# Blinds_Motor_ESP32_w_endstops.net
KiCad netlist of a schematic drawn in EAGLE
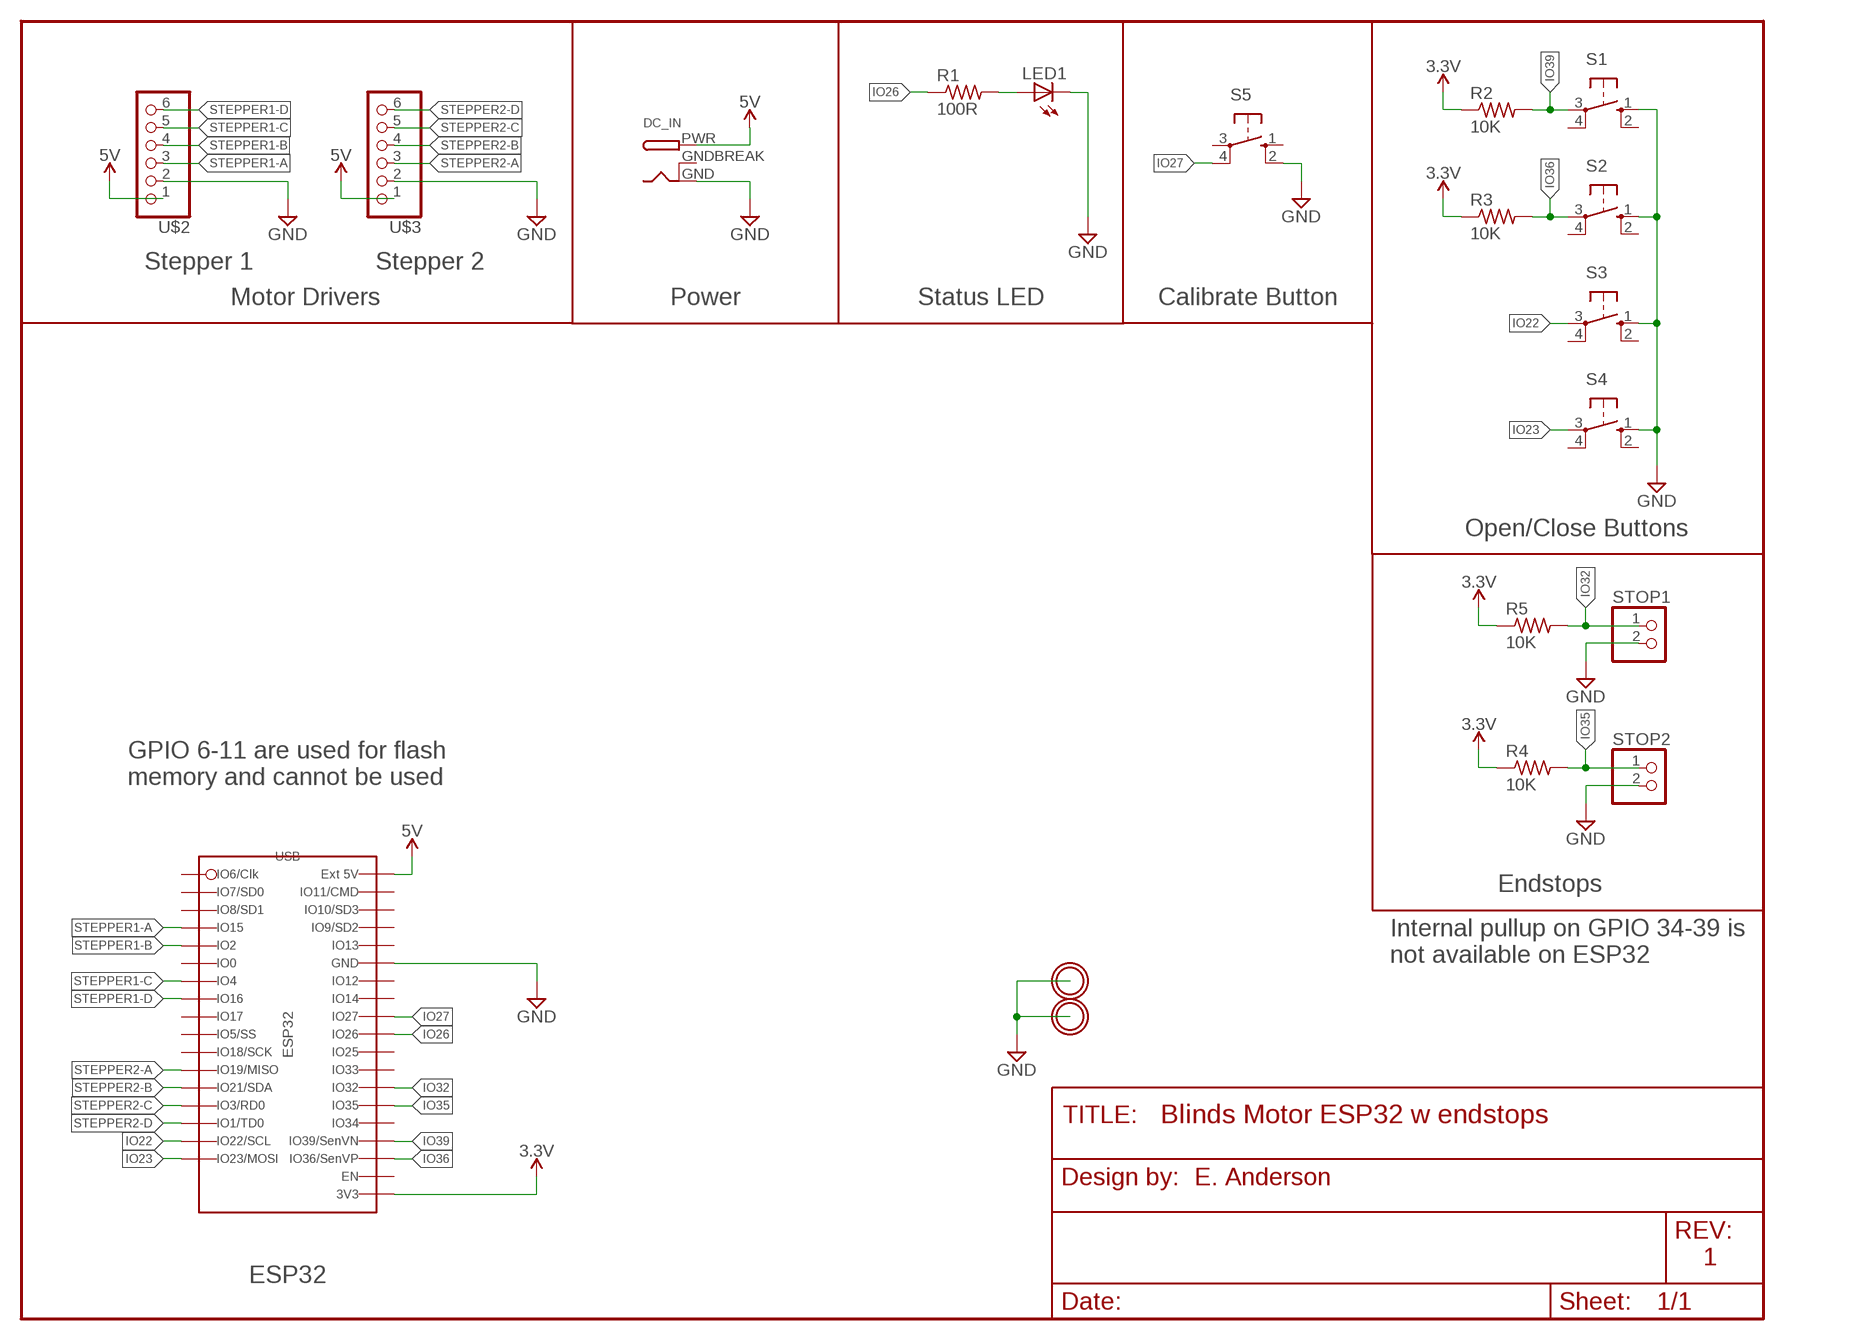
[diagram p0: schematic, sheet 1]

(export (version "E")
  (design (tool "Eeschema 10.0.6"))
  (components
    (comp (ref "DC_IN")
      (value "DCBARRELPTH")
      (footprint "eagle-import:DCJACK_2MM_PTH")
      (libsource (lib "eagle-import") (part "DCBARRELPTH"))
    )
    (comp (ref "LED1")
      (value "LED-CHIPLED_1206_LONG")
      (footprint "eagle-import:CHIPLED_1206_LONG")
      (libsource (lib "eagle-import") (part "LED-CHIPLED_1206_LONG"))
    )
    (comp (ref "R1")
      (value "100R")
      (footprint "eagle-import:R1206")
      (libsource (lib "eagle-import") (part "R_USR1206"))
    )
    (comp (ref "R2")
      (value "10K")
      (footprint "eagle-import:R1206")
      (libsource (lib "eagle-import") (part "R_USR1206"))
    )
    (comp (ref "R3")
      (value "10K")
      (footprint "eagle-import:R1206")
      (libsource (lib "eagle-import") (part "R_USR1206"))
    )
    (comp (ref "R4")
      (value "10K")
      (footprint "eagle-import:R1206")
      (libsource (lib "eagle-import") (part "R_USR1206"))
    )
    (comp (ref "R5")
      (value "10K")
      (footprint "eagle-import:R1206")
      (libsource (lib "eagle-import") (part "R_USR1206"))
    )
    (comp (ref "S1")
      (value "B3F-10XX")
      (footprint "eagle-import:B3F-10XX")
      (fields (field (name "MPN") "B3F-1000"))
      (libsource (lib "eagle-import") (part "B3F-10XX"))
    )
    (comp (ref "S2")
      (value "B3F-10XX")
      (footprint "eagle-import:B3F-10XX")
      (fields (field (name "MPN") "B3F-1000"))
      (libsource (lib "eagle-import") (part "B3F-10XX"))
    )
    (comp (ref "S3")
      (value "B3F-10XX")
      (footprint "eagle-import:B3F-10XX")
      (fields (field (name "MPN") "B3F-1000"))
      (libsource (lib "eagle-import") (part "B3F-10XX"))
    )
    (comp (ref "S4")
      (value "B3F-10XX")
      (footprint "eagle-import:B3F-10XX")
      (fields (field (name "MPN") "B3F-1000"))
      (libsource (lib "eagle-import") (part "B3F-10XX"))
    )
    (comp (ref "S5")
      (value "B3F-10XX")
      (footprint "eagle-import:B3F-10XX")
      (fields (field (name "MPN") "B3F-1000"))
      (libsource (lib "eagle-import") (part "B3F-10XX"))
    )
    (comp (ref "STOP1")
      (value "1X2_HEADER_LONG")
      (footprint "eagle-import:1X02")
      (libsource (lib "eagle-import") (part "1X2_HEADER_LONG"))
    )
    (comp (ref "STOP2")
      (value "1X2_HEADER_LONG")
      (footprint "eagle-import:1X02")
      (libsource (lib "eagle-import") (part "1X2_HEADER_LONG"))
    )
    (comp (ref "U$2")
      (value "Stepper 1")
      (footprint "eagle-import:1X06")
      (libsource (lib "eagle-import") (part "1X6_HEADER_LONG"))
    )
    (comp (ref "U$3")
      (value "Stepper 2")
      (footprint "eagle-import:1X06")
      (libsource (lib "eagle-import") (part "1X6_HEADER_LONG"))
    )
    (comp (ref "U$5")
      (value "MICROBUILDER_MOUNTINGHOLE3.0THIN")
      (footprint "eagle-import:MICROBUILDER_MOUNTINGHOLE_3.0_PLATEDTHIN")
      (libsource (lib "eagle-import") (part "MICROBUILDER_MOUNTINGHOLE3.0THIN"))
    )
    (comp (ref "U$6")
      (value "MICROBUILDER_MOUNTINGHOLE3.0THIN")
      (footprint "eagle-import:MICROBUILDER_MOUNTINGHOLE_3.0_PLATEDTHIN")
      (libsource (lib "eagle-import") (part "MICROBUILDER_MOUNTINGHOLE3.0THIN"))
    )
    (comp (ref "U$7")
      (value "ESP32-DEV")
      (footprint "eagle-import:ESP32_DEV")
      (libsource (lib "eagle-import") (part "ESP32-DEV"))
    )
  )
  (nets
    (net (code "1") (name "/GNDBREAK") (class "Default")
      (node (ref "DC_IN") (pin "GNDBREAK") (pinfunction "GNDBREAK_GNDBREAK") (pintype "power_in"))
    )
    (net (code "2") (name "3.3V") (class "Default")
      (node (ref "R2") (pin "1") (pinfunction "1_1") (pintype "passive"))
      (node (ref "R3") (pin "1") (pinfunction "1_1") (pintype "passive"))
      (node (ref "R4") (pin "1") (pinfunction "1_1") (pintype "passive"))
      (node (ref "R5") (pin "1") (pinfunction "1_1") (pintype "passive"))
      (node (ref "U$7") (pin "3V3") (pinfunction "3V3_3V3") (pintype "power_in"))
    )
    (net (code "3") (name "5V") (class "Default")
      (node (ref "DC_IN") (pin "PWR") (pinfunction "PWR_PWR") (pintype "power_in"))
      (node (ref "U$2") (pin "1") (pinfunction "1_1") (pintype "passive"))
      (node (ref "U$3") (pin "1") (pinfunction "1_1") (pintype "passive"))
      (node (ref "U$7") (pin "5V") (pinfunction "EXT_5V_5V") (pintype "power_in"))
    )
    (net (code "4") (name "GND") (class "Default")
      (node (ref "DC_IN") (pin "GND") (pinfunction "GND_GND") (pintype "power_in"))
      (node (ref "LED1") (pin "C") (pinfunction "C_C") (pintype "passive"))
      (node (ref "S1") (pin "1") (pinfunction "S_1") (pintype "passive"))
      (node (ref "S2") (pin "1") (pinfunction "S_1") (pintype "passive"))
      (node (ref "S3") (pin "1") (pinfunction "S_1") (pintype "passive"))
      (node (ref "S4") (pin "1") (pinfunction "S_1") (pintype "passive"))
      (node (ref "S5") (pin "2") (pinfunction "S1_2") (pintype "passive"))
      (node (ref "STOP1") (pin "2") (pinfunction "2_2") (pintype "passive"))
      (node (ref "STOP2") (pin "2") (pinfunction "2_2") (pintype "passive"))
      (node (ref "U$2") (pin "2") (pinfunction "2_2") (pintype "passive"))
      (node (ref "U$3") (pin "2") (pinfunction "2_2") (pintype "passive"))
      (node (ref "U$7") (pin "GND") (pinfunction "GND1_GND") (pintype "bidirectional"))
      (node (ref "U$7") (pin "GND1") (pinfunction "GND1_GND1") (pintype "bidirectional"))
      (node (ref "U$7") (pin "GND2") (pinfunction "GND1_GND2") (pintype "bidirectional"))
    )
    (net (code "5") (name "IO22") (class "Default")
      (node (ref "S3") (pin "3") (pinfunction "P_3") (pintype "passive"))
      (node (ref "U$7") (pin "IO22") (pinfunction "IO22_IO22") (pintype "bidirectional"))
    )
    (net (code "6") (name "IO23") (class "Default")
      (node (ref "S4") (pin "3") (pinfunction "P_3") (pintype "passive"))
      (node (ref "U$7") (pin "IO23") (pinfunction "IO23/SCL_IO23") (pintype "bidirectional"))
    )
    (net (code "7") (name "IO26") (class "Default")
      (node (ref "R1") (pin "1") (pinfunction "1_1") (pintype "passive"))
      (node (ref "U$7") (pin "IO26") (pinfunction "IO26_IO26") (pintype "bidirectional"))
    )
    (net (code "8") (name "IO27") (class "Default")
      (node (ref "S5") (pin "4") (pinfunction "P1_4") (pintype "passive"))
      (node (ref "U$7") (pin "IO27") (pinfunction "IO27_IO27") (pintype "bidirectional"))
    )
    (net (code "9") (name "IO32") (class "Default")
      (node (ref "R5") (pin "2") (pinfunction "2_2") (pintype "passive"))
      (node (ref "STOP1") (pin "1") (pinfunction "1_1") (pintype "passive"))
      (node (ref "U$7") (pin "IO32") (pinfunction "IO32_IO32") (pintype "bidirectional"))
    )
    (net (code "10") (name "IO35") (class "Default")
      (node (ref "R4") (pin "2") (pinfunction "2_2") (pintype "passive"))
      (node (ref "STOP2") (pin "1") (pinfunction "1_1") (pintype "passive"))
      (node (ref "U$7") (pin "IO35") (pinfunction "IO35_IO35") (pintype "bidirectional"))
    )
    (net (code "11") (name "IO36") (class "Default")
      (node (ref "R3") (pin "2") (pinfunction "2_2") (pintype "passive"))
      (node (ref "S2") (pin "3") (pinfunction "P_3") (pintype "passive"))
      (node (ref "U$7") (pin "IO36-SVP") (pinfunction "IO36/SVP_IO36-SVP") (pintype "bidirectional"))
    )
    (net (code "12") (name "IO39") (class "Default")
      (node (ref "R2") (pin "2") (pinfunction "2_2") (pintype "passive"))
      (node (ref "S1") (pin "3") (pinfunction "P_3") (pintype "passive"))
      (node (ref "U$7") (pin "IO39-SVN") (pinfunction "IO39/SVN_IO39-SVN") (pintype "bidirectional"))
    )
    (net (code "13") (name "Net-(LED1-PadA)") (class "Default")
      (node (ref "LED1") (pin "A") (pinfunction "A_A") (pintype "passive"))
      (node (ref "R1") (pin "2") (pinfunction "2_2") (pintype "passive"))
    )
    (net (code "14") (name "STEPPER1-A") (class "Default")
      (node (ref "U$2") (pin "3") (pinfunction "3_3") (pintype "passive"))
      (node (ref "U$7") (pin "IO15") (pinfunction "IO15_IO15") (pintype "bidirectional"))
    )
    (net (code "15") (name "STEPPER1-B") (class "Default")
      (node (ref "U$2") (pin "4") (pinfunction "4_4") (pintype "passive"))
      (node (ref "U$7") (pin "IO2") (pinfunction "IO2_IO2") (pintype "bidirectional"))
    )
    (net (code "16") (name "STEPPER1-C") (class "Default")
      (node (ref "U$2") (pin "5") (pinfunction "5_5") (pintype "passive"))
      (node (ref "U$7") (pin "IO4") (pinfunction "IO4_IO4") (pintype "bidirectional"))
    )
    (net (code "17") (name "STEPPER1-D") (class "Default")
      (node (ref "U$2") (pin "6") (pinfunction "6_6") (pintype "passive"))
      (node (ref "U$7") (pin "IO16") (pinfunction "IO16_IO16") (pintype "bidirectional"))
    )
    (net (code "18") (name "STEPPER2-A") (class "Default")
      (node (ref "U$3") (pin "3") (pinfunction "3_3") (pintype "passive"))
      (node (ref "U$7") (pin "IO19") (pinfunction "IO19_IO19") (pintype "bidirectional"))
    )
    (net (code "19") (name "STEPPER2-B") (class "Default")
      (node (ref "U$3") (pin "4") (pinfunction "4_4") (pintype "passive"))
      (node (ref "U$7") (pin "IO21") (pinfunction "IO21/SDA_IO21") (pintype "bidirectional"))
    )
    (net (code "20") (name "STEPPER2-C") (class "Default")
      (node (ref "U$3") (pin "5") (pinfunction "5_5") (pintype "passive"))
      (node (ref "U$7") (pin "IO3-RXD0") (pinfunction "RXD0_IO3-RXD0") (pintype "input"))
    )
    (net (code "21") (name "STEPPER2-D") (class "Default")
      (node (ref "U$3") (pin "6") (pinfunction "6_6") (pintype "passive"))
      (node (ref "U$7") (pin "IO1-TXD0") (pinfunction "TXD0_IO1-TXD0") (pintype "output"))
    )
    (net (code "22") (name "unconnected-(S1-P1-Pad4)") (class "Default")
      (node (ref "S1") (pin "4") (pinfunction "P1_4") (pintype "passive"))
    )
    (net (code "23") (name "unconnected-(S1-S1-Pad2)") (class "Default")
      (node (ref "S1") (pin "2") (pinfunction "S1_2") (pintype "passive"))
    )
    (net (code "24") (name "unconnected-(S2-P1-Pad4)") (class "Default")
      (node (ref "S2") (pin "4") (pinfunction "P1_4") (pintype "passive"))
    )
    (net (code "25") (name "unconnected-(S2-S1-Pad2)") (class "Default")
      (node (ref "S2") (pin "2") (pinfunction "S1_2") (pintype "passive"))
    )
    (net (code "26") (name "unconnected-(S3-P1-Pad4)") (class "Default")
      (node (ref "S3") (pin "4") (pinfunction "P1_4") (pintype "passive"))
    )
    (net (code "27") (name "unconnected-(S3-S1-Pad2)") (class "Default")
      (node (ref "S3") (pin "2") (pinfunction "S1_2") (pintype "passive"))
    )
    (net (code "28") (name "unconnected-(S4-P1-Pad4)") (class "Default")
      (node (ref "S4") (pin "4") (pinfunction "P1_4") (pintype "passive"))
    )
    (net (code "29") (name "unconnected-(S4-S1-Pad2)") (class "Default")
      (node (ref "S4") (pin "2") (pinfunction "S1_2") (pintype "passive"))
    )
    (net (code "30") (name "unconnected-(S5-P-Pad3)") (class "Default")
      (node (ref "S5") (pin "3") (pinfunction "P_3") (pintype "passive"))
    )
    (net (code "31") (name "unconnected-(S5-S-Pad1)") (class "Default")
      (node (ref "S5") (pin "1") (pinfunction "S_1") (pintype "passive"))
    )
    (net (code "32") (name "unconnected-(U$7-CLK-PadIO6-CLK)") (class "Default")
      (node (ref "U$7") (pin "IO6-CLK") (pinfunction "CLK_IO6-CLK") (pintype "bidirectional"))
    )
    (net (code "33") (name "unconnected-(U$7-IO9{slash}SD2-PadIO9-SD2)") (class "Default")
      (node (ref "U$7") (pin "IO9-SD2") (pinfunction "IO9/SD2_IO9-SD2") (pintype "bidirectional"))
    )
    (net (code "34") (name "unconnected-(U$7-IO10{slash}SD3-PadIO10-SD3)") (class "Default")
      (node (ref "U$7") (pin "IO10-SD3") (pinfunction "IO10/SD3_IO10-SD3") (pintype "bidirectional"))
    )
    (net (code "35") (name "unconnected-(U$7-IO11{slash}CMD-PadIO11-CMD)") (class "Default")
      (node (ref "U$7") (pin "IO11-CMD") (pinfunction "IO11/CMD_IO11-CMD") (pintype "bidirectional"))
    )
    (net (code "36") (name "unconnected-(U$7-PadEN)") (class "Default")
      (node (ref "U$7") (pin "EN") (pinfunction "EN_EN") (pintype "bidirectional"))
    )
    (net (code "37") (name "unconnected-(U$7-PadIO0)") (class "Default")
      (node (ref "U$7") (pin "IO0") (pinfunction "IO0_IO0") (pintype "bidirectional"))
    )
    (net (code "38") (name "unconnected-(U$7-PadIO5)") (class "Default")
      (node (ref "U$7") (pin "IO5") (pinfunction "IO5_IO5") (pintype "bidirectional"))
    )
    (net (code "39") (name "unconnected-(U$7-PadIO12)") (class "Default")
      (node (ref "U$7") (pin "IO12") (pinfunction "IO12_IO12") (pintype "bidirectional"))
    )
    (net (code "40") (name "unconnected-(U$7-PadIO13)") (class "Default")
      (node (ref "U$7") (pin "IO13") (pinfunction "IO13_IO13") (pintype "bidirectional"))
    )
    (net (code "41") (name "unconnected-(U$7-PadIO14)") (class "Default")
      (node (ref "U$7") (pin "IO14") (pinfunction "IO14_IO14") (pintype "bidirectional"))
    )
    (net (code "42") (name "unconnected-(U$7-PadIO17)") (class "Default")
      (node (ref "U$7") (pin "IO17") (pinfunction "IO17_IO17") (pintype "bidirectional"))
    )
    (net (code "43") (name "unconnected-(U$7-PadIO18)") (class "Default")
      (node (ref "U$7") (pin "IO18") (pinfunction "IO18_IO18") (pintype "bidirectional"))
    )
    (net (code "44") (name "unconnected-(U$7-PadIO25)") (class "Default")
      (node (ref "U$7") (pin "IO25") (pinfunction "IO25_IO25") (pintype "bidirectional"))
    )
    (net (code "45") (name "unconnected-(U$7-PadIO33)") (class "Default")
      (node (ref "U$7") (pin "IO33") (pinfunction "IO33_IO33") (pintype "bidirectional"))
    )
    (net (code "46") (name "unconnected-(U$7-PadIO34)") (class "Default")
      (node (ref "U$7") (pin "IO34") (pinfunction "IO34_IO34") (pintype "bidirectional"))
    )
    (net (code "47") (name "unconnected-(U$7-SD0-PadIO7-SD0)") (class "Default")
      (node (ref "U$7") (pin "IO7-SD0") (pinfunction "SD0_IO7-SD0") (pintype "bidirectional"))
    )
    (net (code "48") (name "unconnected-(U$7-SD1-PadIO8-SD1)") (class "Default")
      (node (ref "U$7") (pin "IO8-SD1") (pinfunction "SD1_IO8-SD1") (pintype "bidirectional"))
    )
  )
)
